# usb.net
KiCad netlist of a schematic drawn in Altium Designer
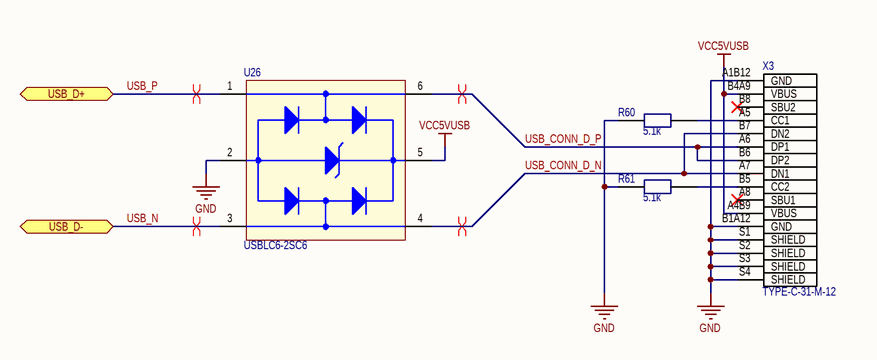
[diagram p0: usb.SchDoc]

(export (version "E")
  (design (tool "Eeschema 10.0.6"))
  (components
    (comp (ref "R60")
      (value "5.1k")
      (footprint "R_0603")
      (description "Resistor")
      (fields (field (name "PART NUMBER") "RC0603JR-075K1L"))
      (libsource (lib "resistors") (part "RES_SMD"))
    )
    (comp (ref "R61")
      (value "5.1k")
      (footprint "R_0603")
      (description "Resistor")
      (fields (field (name "PART NUMBER") "RC0603JR-075K1L"))
      (libsource (lib "resistors") (part "RES_SMD"))
    )
    (comp (ref "U26")
      (value "USBLC6-2SC6")
      (footprint "diode:SOT95P280X145-6N")
      (description "17V Clamp 5A (8/20Âµs) Ipp Tvs Diode Surface Mount SOT-23-6")
      (fields (field (name "MF") "STMicroelectronics"))
      (libsource (lib "diode") (part "USBLC6-2SC6"))
    )
    (comp (ref "X3")
      (value "TYPE-C-31-M-12")
      (footprint "connectors_socets:HRO_TYPE-C-31-M-12")
      (description "USB Connectors 24 Receptacle 1 8.94*7.3mm RoHS")
      (libsource (lib "connectors_socets") (part "TYPE-C-31-M-12"))
    )
  )
  (nets
    (net (code "1") (name "/USB_CONN_D_N") (class "Default")
      (node (ref "U26") (pin "4") (pinfunction "I/O2_OUT_4") (pintype "passive"))
      (node (ref "X3") (pin "A7") (pinfunction "DN1_A7") (pintype "passive"))
      (node (ref "X3") (pin "B7") (pinfunction "DN2_B7") (pintype "passive"))
    )
    (net (code "2") (name "/USB_CONN_D_P") (class "Default")
      (node (ref "U26") (pin "6") (pinfunction "I/O1_OUT_6") (pintype "passive"))
      (node (ref "X3") (pin "A6") (pinfunction "DP1_A6") (pintype "passive"))
      (node (ref "X3") (pin "B6") (pinfunction "DP2_B6") (pintype "passive"))
    )
    (net (code "3") (name "/USB_N") (class "Default")
      (node (ref "U26") (pin "3") (pinfunction "I/O2_IN_3") (pintype "passive"))
    )
    (net (code "4") (name "/USB_P") (class "Default")
      (node (ref "U26") (pin "1") (pinfunction "I/O1_IN_1") (pintype "passive"))
    )
    (net (code "5") (name "GND") (class "Default")
      (node (ref "R60") (pin "1") (pinfunction "1_1") (pintype "passive"))
      (node (ref "R61") (pin "1") (pinfunction "1_1") (pintype "passive"))
      (node (ref "U26") (pin "2") (pinfunction "GND_2") (pintype "passive"))
      (node (ref "X3") (pin "A1B12") (pinfunction "GND_A1B12") (pintype "passive"))
      (node (ref "X3") (pin "B1A12") (pinfunction "GND_B1A12") (pintype "passive"))
      (node (ref "X3") (pin "S1") (pinfunction "SHIELD_S1") (pintype "passive"))
      (node (ref "X3") (pin "S2") (pinfunction "SHIELD_S2") (pintype "passive"))
      (node (ref "X3") (pin "S3") (pinfunction "SHIELD_S3") (pintype "passive"))
      (node (ref "X3") (pin "S4") (pinfunction "SHIELD_S4") (pintype "passive"))
    )
    (net (code "6") (name "Net-(X3-CC1)") (class "Default")
      (node (ref "R60") (pin "2") (pinfunction "2_2") (pintype "passive"))
      (node (ref "X3") (pin "A5") (pinfunction "CC1_A5") (pintype "passive"))
    )
    (net (code "7") (name "Net-(X3-CC2)") (class "Default")
      (node (ref "R61") (pin "2") (pinfunction "2_2") (pintype "passive"))
      (node (ref "X3") (pin "B5") (pinfunction "CC2_B5") (pintype "passive"))
    )
    (net (code "8") (name "VCC5VUSB") (class "Default")
      (node (ref "U26") (pin "5") (pinfunction "VBUS_5") (pintype "passive"))
      (node (ref "X3") (pin "A4B9") (pinfunction "VBUS_A4B9") (pintype "passive"))
      (node (ref "X3") (pin "B4A9") (pinfunction "VBUS_B4A9") (pintype "passive"))
    )
    (net (code "9") (name "unconnected-(X3-SBU1-PadA8)") (class "Default")
      (node (ref "X3") (pin "A8") (pinfunction "SBU1_A8") (pintype "passive+no_connect"))
    )
    (net (code "10") (name "unconnected-(X3-SBU2-PadB8)") (class "Default")
      (node (ref "X3") (pin "B8") (pinfunction "SBU2_B8") (pintype "passive+no_connect"))
    )
  )
)
